# flashlight.net
KiCad netlist of a schematic drawn in EAGLE
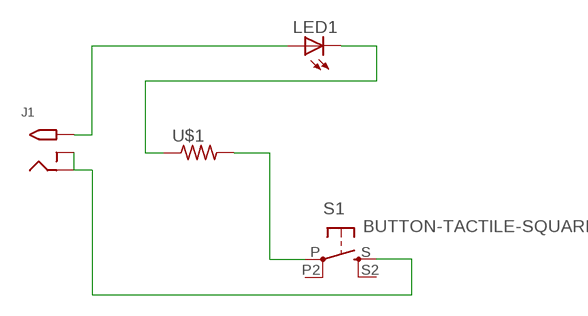
[diagram p0: schematic, sheet 1]

(export (version "E")
  (design (tool "Eeschema 10.0.6"))
  (components
    (comp (ref "J1")
      (value "2.1MMJACKTHM")
      (footprint "eagle-import:PJ-102A")
      (libsource (lib "eagle-import") (part "2.1MMJACKTHM"))
    )
    (comp (ref "LED1")
      (value "LED5MM")
      (footprint "eagle-import:LED5MM")
      (libsource (lib "eagle-import") (part "LED5MM"))
    )
    (comp (ref "S1")
      (value "BUTTON-TACTILE-SQUARE")
      (footprint "eagle-import:BUTTON-TACTILE-SQUARE-ADAFRUIT1010")
      (libsource (lib "eagle-import") (part "BUTTON-TACTILE-SQUARE"))
    )
    (comp (ref "U$1")
      (value "RESISTORTH-1/4W-CARBON")
      (footprint "eagle-import:RESAD1160W55L680D260_HS")
      (libsource (lib "eagle-import") (part "RESISTORTH-1/4W-CARBON"))
    )
  )
  (nets
    (net (code "1") (name "Net-(J1-PadRING)") (class "Default")
      (node (ref "J1") (pin "RING") (pinfunction "RING_RING") (pintype "bidirectional"))
      (node (ref "J1") (pin "RING_SW") (pinfunction "RING_SW_RING_SW") (pintype "bidirectional"))
      (node (ref "S1") (pin "S") (pinfunction "S_S") (pintype "passive"))
    )
    (net (code "2") (name "Net-(J1-PadTIP)") (class "Default")
      (node (ref "J1") (pin "TIP") (pinfunction "TIP_TIP") (pintype "bidirectional"))
      (node (ref "LED1") (pin "A") (pinfunction "A_A") (pintype "passive"))
    )
    (net (code "3") (name "Net-(LED1-C)") (class "Default")
      (node (ref "LED1") (pin "K") (pinfunction "C_K") (pintype "passive"))
      (node (ref "U$1") (pin "1") (pinfunction "1_1") (pintype "passive"))
    )
    (net (code "4") (name "Net-(S1-PadP)") (class "Default")
      (node (ref "S1") (pin "P") (pinfunction "P_P") (pintype "passive"))
      (node (ref "U$1") (pin "2") (pinfunction "2_2") (pintype "passive"))
    )
    (net (code "5") (name "unconnected-(S1-P1-PadP2)") (class "Default")
      (node (ref "S1") (pin "P2") (pinfunction "P1_P2") (pintype "passive"))
    )
    (net (code "6") (name "unconnected-(S1-S1-PadS2)") (class "Default")
      (node (ref "S1") (pin "S2") (pinfunction "S1_S2") (pintype "passive"))
    )
  )
)
